# Schematic.net
KiCad netlist of a schematic drawn in EAGLE
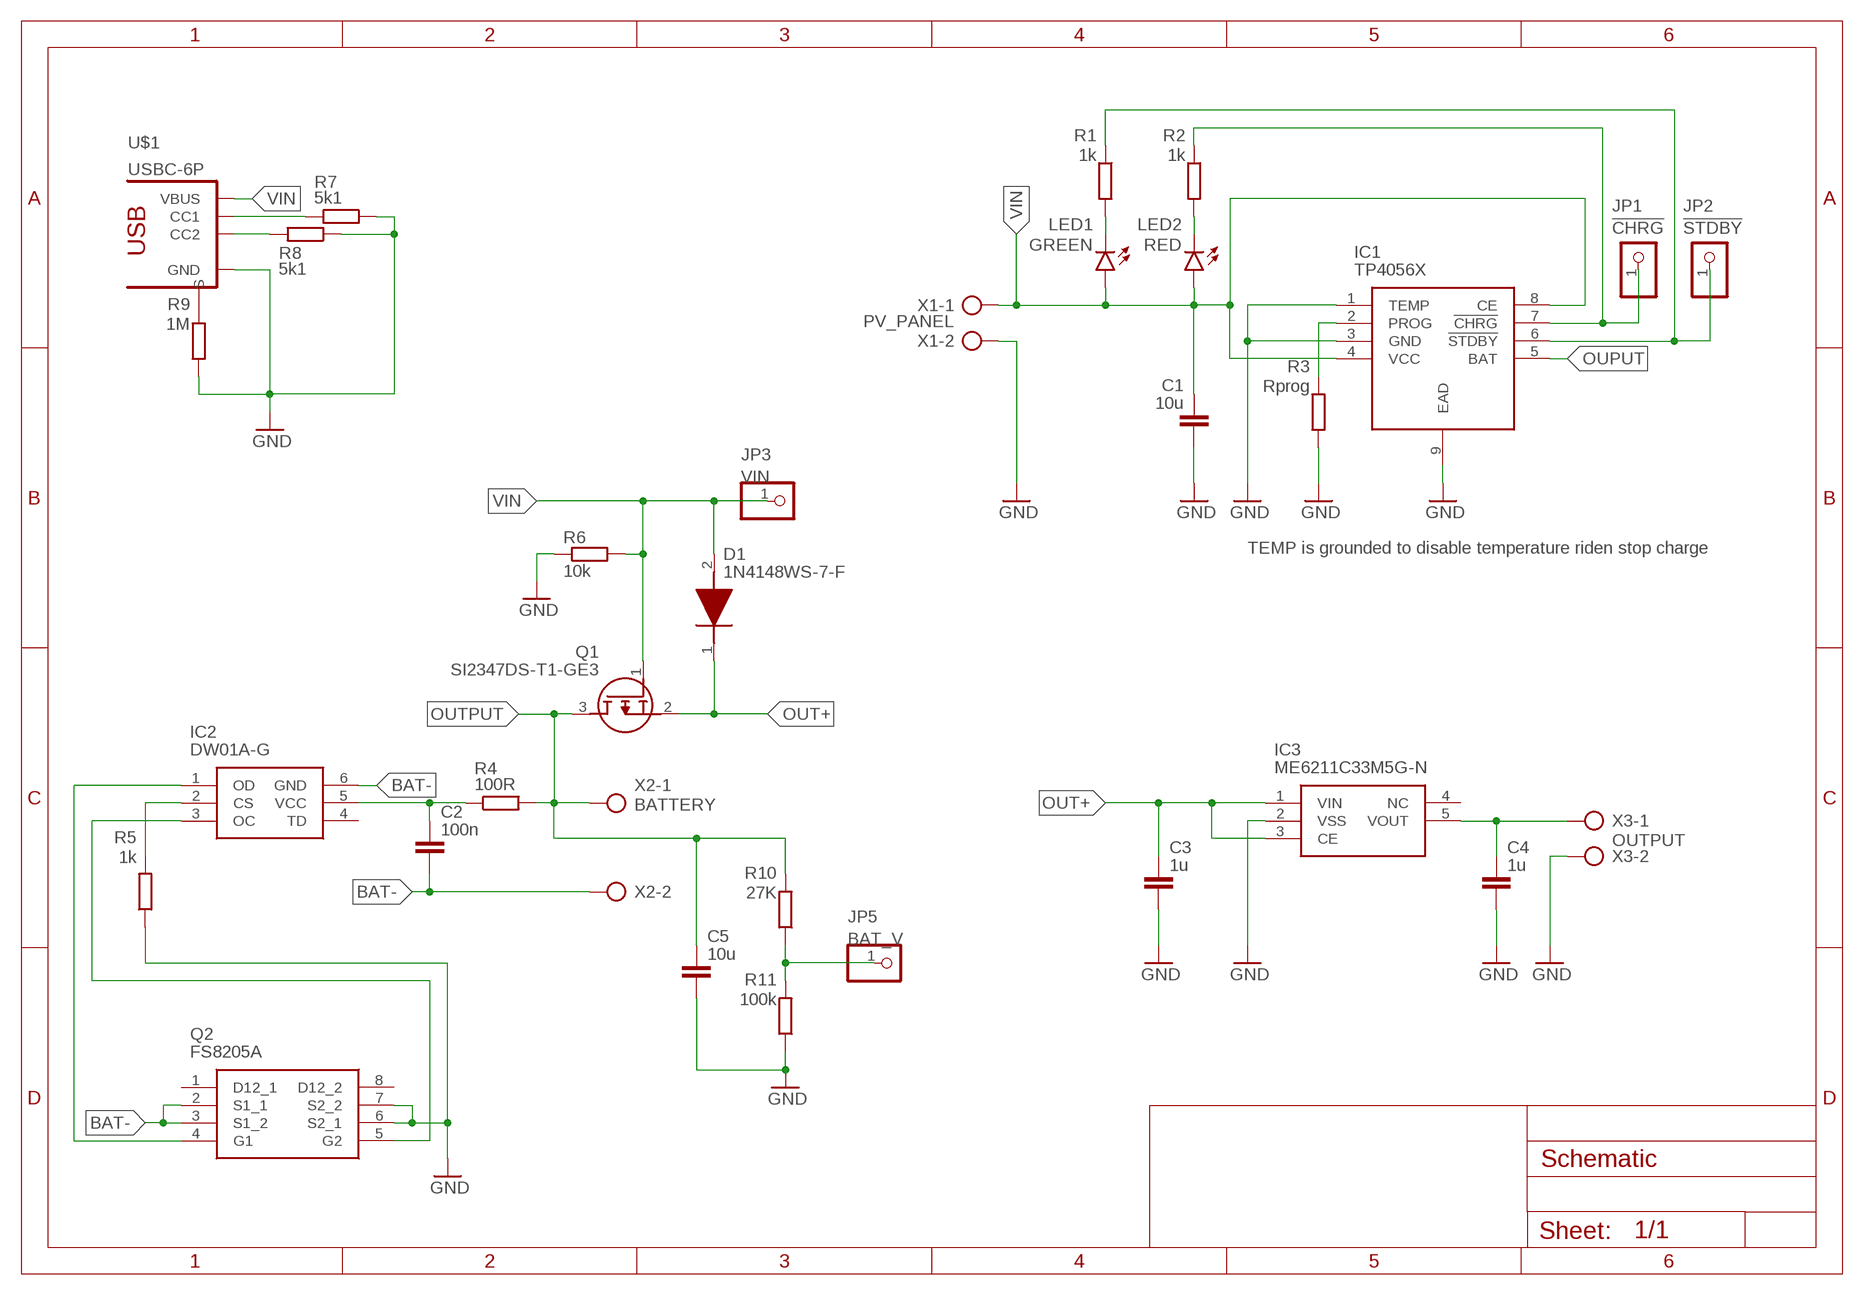
[diagram p0: schematic, sheet 1]

(export (version "E")
  (design (tool "Eeschema 10.0.6"))
  (components
    (comp (ref "C1")
      (value "10u")
      (footprint "eagle-import:C0805")
      (libsource (lib "eagle-import") (part "C-EUC0805"))
    )
    (comp (ref "C2")
      (value "100n")
      (footprint "eagle-import:C0805")
      (libsource (lib "eagle-import") (part "C-EUC0805"))
    )
    (comp (ref "C3")
      (value "1u")
      (footprint "eagle-import:C0805")
      (libsource (lib "eagle-import") (part "C-EUC0805"))
    )
    (comp (ref "C4")
      (value "1u")
      (footprint "eagle-import:C0805")
      (libsource (lib "eagle-import") (part "C-EUC0805"))
    )
    (comp (ref "C5")
      (value "10u")
      (footprint "eagle-import:C0805")
      (libsource (lib "eagle-import") (part "C-EUC0805"))
    )
    (comp (ref "D1")
      (value "1N4148WS-7-F")
      (footprint "eagle-import:SOD2513X120N")
      (fields (field (name "MOUSER_PART_NUMBER") "621-1N4148WS-F"))
      (libsource (lib "eagle-import") (part "1N4148WS-7-F"))
    )
    (comp (ref "IC1")
      (value "TP4056X")
      (footprint "eagle-import:SOIC127P600X175-9N")
      (libsource (lib "eagle-import") (part "TP4056X"))
    )
    (comp (ref "IC2")
      (value "DW01A-G")
      (footprint "eagle-import:SOT95P280X135-6N")
      (libsource (lib "eagle-import") (part "DW01A-G"))
    )
    (comp (ref "IC3")
      (value "ME6211C33M5G-N")
      (footprint "eagle-import:SOT95P270X145-5N")
      (libsource (lib "eagle-import") (part "ME6211C33M5G-N"))
    )
    (comp (ref "JP1")
      (value "!CHRG")
      (footprint "eagle-import:1X01")
      (libsource (lib "eagle-import") (part "PINHD-1X1"))
    )
    (comp (ref "JP2")
      (value "!STDBY")
      (footprint "eagle-import:1X01")
      (libsource (lib "eagle-import") (part "PINHD-1X1"))
    )
    (comp (ref "JP3")
      (value "VIN")
      (footprint "eagle-import:1X01")
      (fields (field (name "SPICEPREFIX") "X"))
      (libsource (lib "eagle-import") (part "PINHD-1X1"))
    )
    (comp (ref "JP5")
      (value "BAT_V")
      (footprint "eagle-import:1X01")
      (libsource (lib "eagle-import") (part "PINHD-1X1"))
    )
    (comp (ref "LED1")
      (value "GREEN")
      (footprint "eagle-import:CHIPLED_0805")
      (libsource (lib "eagle-import") (part "LEDCHIPLED_0805"))
    )
    (comp (ref "LED2")
      (value "RED")
      (footprint "eagle-import:CHIPLED_0805")
      (libsource (lib "eagle-import") (part "LEDCHIPLED_0805"))
    )
    (comp (ref "Q1")
      (value "SI2347DS-T1-GE3")
      (footprint "eagle-import:SOT95P237X112-3N")
      (fields
        (field (name "MANUFACTURER_PART_NUMBER") "Si2347DS-T1-GE3")
        (field (name "MOUSER_PART_NUMBER") "78-SI2347DS-T1-GE3")
      )
      (libsource (lib "eagle-import") (part "SI2347DS-T1-GE3"))
    )
    (comp (ref "Q2")
      (value "FS8205A")
      (footprint "eagle-import:SOP65P640X120-8N")
      (libsource (lib "eagle-import") (part "FS8205A"))
    )
    (comp (ref "R1")
      (value "1k")
      (footprint "eagle-import:R0805")
      (libsource (lib "eagle-import") (part "R-EU_R0805"))
    )
    (comp (ref "R2")
      (value "1k")
      (footprint "eagle-import:R0805")
      (libsource (lib "eagle-import") (part "R-EU_R0805"))
    )
    (comp (ref "R3")
      (value "Rprog")
      (footprint "eagle-import:R0805")
      (libsource (lib "eagle-import") (part "R-EU_R0805"))
    )
    (comp (ref "R4")
      (value "100R")
      (footprint "eagle-import:R0805")
      (libsource (lib "eagle-import") (part "R-EU_R0805"))
    )
    (comp (ref "R5")
      (value "1k")
      (footprint "eagle-import:R0805")
      (libsource (lib "eagle-import") (part "R-EU_R0805"))
    )
    (comp (ref "R6")
      (value "10k")
      (footprint "eagle-import:R0805")
      (libsource (lib "eagle-import") (part "R-EU_R0805"))
    )
    (comp (ref "R7")
      (value "5k1")
      (footprint "eagle-import:R0805")
      (libsource (lib "eagle-import") (part "R-EU_R0805"))
    )
    (comp (ref "R8")
      (value "5k1")
      (footprint "eagle-import:R0805")
      (libsource (lib "eagle-import") (part "R-EU_R0805"))
    )
    (comp (ref "R9")
      (value "1M")
      (footprint "eagle-import:R0805")
      (libsource (lib "eagle-import") (part "R-EU_R0805"))
    )
    (comp (ref "R10")
      (value "27K")
      (footprint "eagle-import:R0805")
      (libsource (lib "eagle-import") (part "R-EU_R0805"))
    )
    (comp (ref "R11")
      (value "100k")
      (footprint "eagle-import:R0805")
      (libsource (lib "eagle-import") (part "R-EU_R0805"))
    )
    (comp (ref "U$1")
      (value "USBC-6P")
      (footprint "eagle-import:USCX-06FX-XXMX-01")
      (libsource (lib "eagle-import") (part "USBC-6P"))
    )
    (comp (ref "X1")
      (value "PV_PANEL")
      (footprint "eagle-import:AK300_2")
      (libsource (lib "eagle-import") (part "AK300/2"))
    )
    (comp (ref "X2")
      (value "BATTERY")
      (footprint "eagle-import:AK300_2")
      (libsource (lib "eagle-import") (part "AK300/2"))
    )
    (comp (ref "X3")
      (value "OUTPUT")
      (footprint "eagle-import:AK300_2")
      (libsource (lib "eagle-import") (part "AK300/2"))
    )
  )
  (nets
    (net (code "1") (name "BAT-") (class "Default")
      (node (ref "C2") (pin "2") (pinfunction "2_2") (pintype "passive"))
      (node (ref "IC2") (pin "6") (pinfunction "GND_6") (pintype "bidirectional"))
      (node (ref "Q2") (pin "2") (pinfunction "S1_1_2") (pintype "bidirectional"))
      (node (ref "Q2") (pin "3") (pinfunction "S1_2_3") (pintype "bidirectional"))
      (node (ref "X2") (pin "2") (pinfunction "KL_2") (pintype "passive"))
    )
    (net (code "2") (name "GND") (class "Default")
      (node (ref "C1") (pin "2") (pinfunction "2_2") (pintype "passive"))
      (node (ref "C3") (pin "2") (pinfunction "2_2") (pintype "passive"))
      (node (ref "C4") (pin "2") (pinfunction "2_2") (pintype "passive"))
      (node (ref "C5") (pin "2") (pinfunction "2_2") (pintype "passive"))
      (node (ref "IC1") (pin "1") (pinfunction "TEMP_1") (pintype "bidirectional"))
      (node (ref "IC1") (pin "3") (pinfunction "GND_3") (pintype "bidirectional"))
      (node (ref "IC1") (pin "9") (pinfunction "EAD_9") (pintype "bidirectional"))
      (node (ref "IC3") (pin "2") (pinfunction "VSS_2") (pintype "bidirectional"))
      (node (ref "Q2") (pin "6") (pinfunction "S2_1_6") (pintype "bidirectional"))
      (node (ref "Q2") (pin "7") (pinfunction "S2_2_7") (pintype "bidirectional"))
      (node (ref "R11") (pin "1") (pinfunction "1_1") (pintype "passive"))
      (node (ref "R3") (pin "2") (pinfunction "2_2") (pintype "passive"))
      (node (ref "R5") (pin "1") (pinfunction "1_1") (pintype "passive"))
      (node (ref "R6") (pin "1") (pinfunction "1_1") (pintype "passive"))
      (node (ref "R7") (pin "1") (pinfunction "1_1") (pintype "passive"))
      (node (ref "R8") (pin "1") (pinfunction "1_1") (pintype "passive"))
      (node (ref "R9") (pin "2") (pinfunction "2_2") (pintype "passive"))
      (node (ref "U$1") (pin "GND1") (pinfunction "GND_GND1") (pintype "power_in"))
      (node (ref "U$1") (pin "GND2") (pinfunction "GND_GND2") (pintype "power_in"))
      (node (ref "X1") (pin "2") (pinfunction "KL_2") (pintype "passive"))
      (node (ref "X3") (pin "2") (pinfunction "KL_2") (pintype "passive"))
    )
    (net (code "3") (name "Net-(IC1-PROG)") (class "Default")
      (node (ref "IC1") (pin "2") (pinfunction "PROG_2") (pintype "bidirectional"))
      (node (ref "R3") (pin "1") (pinfunction "1_1") (pintype "passive"))
    )
    (net (code "4") (name "Net-(IC1-~{CHRG})") (class "Default")
      (node (ref "IC1") (pin "7") (pinfunction "~{CHRG}_7") (pintype "bidirectional"))
      (node (ref "JP1") (pin "1") (pinfunction "1_1") (pintype "passive"))
      (node (ref "R2") (pin "1") (pinfunction "1_1") (pintype "passive"))
    )
    (net (code "5") (name "Net-(IC1-~{STDBY})") (class "Default")
      (node (ref "IC1") (pin "6") (pinfunction "~{STDBY}_6") (pintype "bidirectional"))
      (node (ref "JP2") (pin "1") (pinfunction "1_1") (pintype "passive"))
      (node (ref "R1") (pin "1") (pinfunction "1_1") (pintype "passive"))
    )
    (net (code "6") (name "Net-(IC2-CS)") (class "Default")
      (node (ref "IC2") (pin "2") (pinfunction "CS_2") (pintype "bidirectional"))
      (node (ref "R5") (pin "2") (pinfunction "2_2") (pintype "passive"))
    )
    (net (code "7") (name "Net-(IC2-OC)") (class "Default")
      (node (ref "IC2") (pin "3") (pinfunction "OC_3") (pintype "bidirectional"))
      (node (ref "Q2") (pin "5") (pinfunction "G2_5") (pintype "bidirectional"))
    )
    (net (code "8") (name "Net-(IC2-OD)") (class "Default")
      (node (ref "IC2") (pin "1") (pinfunction "OD_1") (pintype "bidirectional"))
      (node (ref "Q2") (pin "4") (pinfunction "G1_4") (pintype "bidirectional"))
    )
    (net (code "9") (name "Net-(IC2-VCC)") (class "Default")
      (node (ref "C2") (pin "1") (pinfunction "1_1") (pintype "passive"))
      (node (ref "IC2") (pin "5") (pinfunction "VCC_5") (pintype "bidirectional"))
      (node (ref "R4") (pin "1") (pinfunction "1_1") (pintype "passive"))
    )
    (net (code "10") (name "Net-(IC3-VOUT)") (class "Default")
      (node (ref "C4") (pin "1") (pinfunction "1_1") (pintype "passive"))
      (node (ref "IC3") (pin "5") (pinfunction "VOUT_5") (pintype "bidirectional"))
      (node (ref "X3") (pin "1") (pinfunction "KL_1") (pintype "passive"))
    )
    (net (code "11") (name "Net-(JP5-Pad1)") (class "Default")
      (node (ref "JP5") (pin "1") (pinfunction "1_1") (pintype "passive"))
      (node (ref "R10") (pin "1") (pinfunction "1_1") (pintype "passive"))
      (node (ref "R11") (pin "2") (pinfunction "2_2") (pintype "passive"))
    )
    (net (code "12") (name "Net-(LED1-PadC)") (class "Default")
      (node (ref "LED1") (pin "C") (pinfunction "C_C") (pintype "passive"))
      (node (ref "R1") (pin "2") (pinfunction "2_2") (pintype "passive"))
    )
    (net (code "13") (name "Net-(LED2-PadC)") (class "Default")
      (node (ref "LED2") (pin "C") (pinfunction "C_C") (pintype "passive"))
      (node (ref "R2") (pin "2") (pinfunction "2_2") (pintype "passive"))
    )
    (net (code "14") (name "Net-(R7-Pad2)") (class "Default")
      (node (ref "R7") (pin "2") (pinfunction "2_2") (pintype "passive"))
      (node (ref "U$1") (pin "CC1") (pinfunction "CC1_CC1") (pintype "bidirectional"))
    )
    (net (code "15") (name "Net-(R8-Pad2)") (class "Default")
      (node (ref "R8") (pin "2") (pinfunction "2_2") (pintype "passive"))
      (node (ref "U$1") (pin "CC2") (pinfunction "CC2_CC2") (pintype "bidirectional"))
    )
    (net (code "16") (name "Net-(R9-Pad1)") (class "Default")
      (node (ref "R9") (pin "1") (pinfunction "1_1") (pintype "passive"))
      (node (ref "U$1") (pin "SHIELD1") (pinfunction "S_SHIELD1") (pintype "passive"))
      (node (ref "U$1") (pin "SHIELD2") (pinfunction "S_SHIELD2") (pintype "passive"))
      (node (ref "U$1") (pin "SHIELD3") (pinfunction "S_SHIELD3") (pintype "passive"))
      (node (ref "U$1") (pin "SHIELD4") (pinfunction "S_SHIELD4") (pintype "passive"))
    )
    (net (code "17") (name "OUPUT") (class "Default")
      (node (ref "IC1") (pin "5") (pinfunction "BAT_5") (pintype "bidirectional"))
    )
    (net (code "18") (name "OUT+") (class "Default")
      (node (ref "C3") (pin "1") (pinfunction "1_1") (pintype "passive"))
      (node (ref "D1") (pin "1") (pinfunction "K_1") (pintype "bidirectional"))
      (node (ref "IC3") (pin "1") (pinfunction "VIN_1") (pintype "bidirectional"))
      (node (ref "IC3") (pin "3") (pinfunction "CE_3") (pintype "bidirectional"))
      (node (ref "Q1") (pin "2") (pinfunction "S_2") (pintype "bidirectional"))
    )
    (net (code "19") (name "OUTPUT") (class "Default")
      (node (ref "C5") (pin "1") (pinfunction "1_1") (pintype "passive"))
      (node (ref "Q1") (pin "3") (pinfunction "D_3") (pintype "bidirectional"))
      (node (ref "R10") (pin "2") (pinfunction "2_2") (pintype "passive"))
      (node (ref "R4") (pin "2") (pinfunction "2_2") (pintype "passive"))
      (node (ref "X2") (pin "1") (pinfunction "KL_1") (pintype "passive"))
    )
    (net (code "20") (name "VIN") (class "Default")
      (node (ref "C1") (pin "1") (pinfunction "1_1") (pintype "passive"))
      (node (ref "D1") (pin "2") (pinfunction "A_2") (pintype "bidirectional"))
      (node (ref "IC1") (pin "4") (pinfunction "VCC_4") (pintype "bidirectional"))
      (node (ref "IC1") (pin "8") (pinfunction "CE_8") (pintype "bidirectional"))
      (node (ref "JP3") (pin "1") (pinfunction "1_1") (pintype "passive"))
      (node (ref "LED1") (pin "A") (pinfunction "A_A") (pintype "passive"))
      (node (ref "LED2") (pin "A") (pinfunction "A_A") (pintype "passive"))
      (node (ref "Q1") (pin "1") (pinfunction "G_1") (pintype "bidirectional"))
      (node (ref "R6") (pin "2") (pinfunction "2_2") (pintype "passive"))
      (node (ref "U$1") (pin "VBUS1") (pinfunction "VBUS_VBUS1") (pintype "power_in"))
      (node (ref "U$1") (pin "VBUS2") (pinfunction "VBUS_VBUS2") (pintype "power_in"))
      (node (ref "X1") (pin "1") (pinfunction "KL_1") (pintype "passive"))
    )
    (net (code "21") (name "unconnected-(IC2-TD-Pad4)") (class "Default")
      (node (ref "IC2") (pin "4") (pinfunction "TD_4") (pintype "bidirectional"))
    )
    (net (code "22") (name "unconnected-(IC3-NC-Pad4)") (class "Default")
      (node (ref "IC3") (pin "4") (pinfunction "NC_4") (pintype "no_connect"))
    )
    (net (code "23") (name "unconnected-(Q2-D12_1-Pad1)") (class "Default")
      (node (ref "Q2") (pin "1") (pinfunction "D12_1_1") (pintype "bidirectional"))
    )
    (net (code "24") (name "unconnected-(Q2-D12_2-Pad8)") (class "Default")
      (node (ref "Q2") (pin "8") (pinfunction "D12_2_8") (pintype "bidirectional"))
    )
  )
)
